# design.net
KiCad netlist of a schematic drawn in Altium Designer
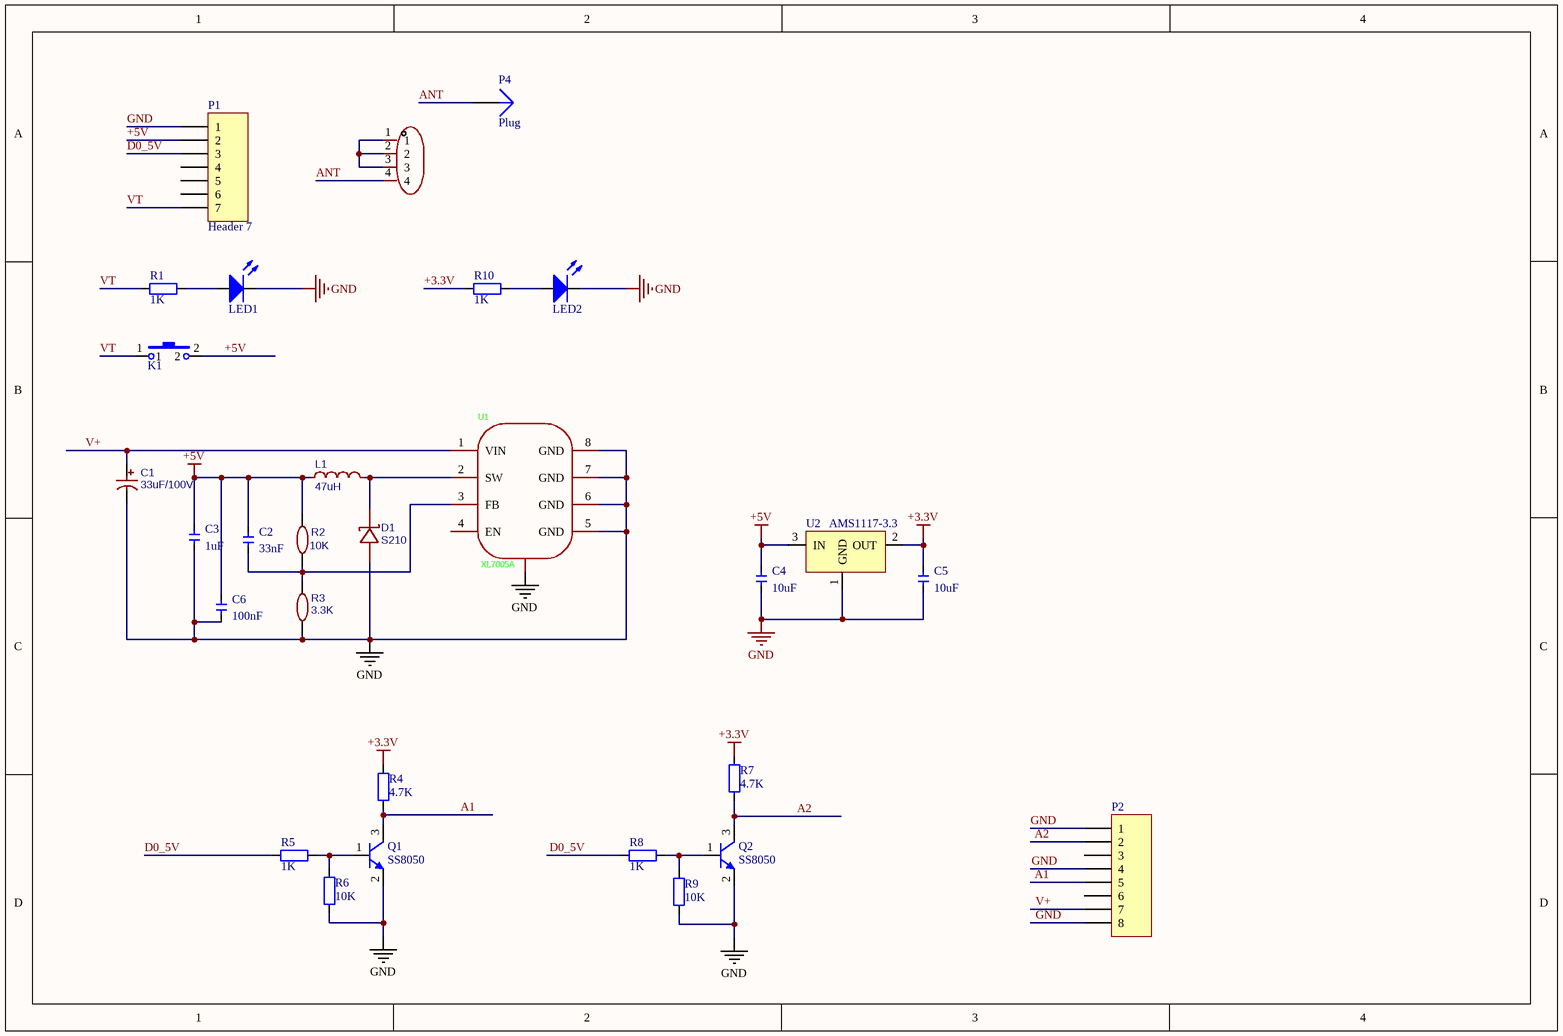
[diagram p0: 遥控.SchDoc]

(export (version "E")
  (design (tool "Eeschema 10.0.6"))
  (components
    (comp (ref "C1")
      (value "33uF/100V")
      (footprint "25V330UF-ZC")
      (fields
        (field (name "MANUFACTURER") "ValuePro")
        (field (name "MANUFACTURER PART") "470uF 35V 10*15Green high frequency")
      )
      (libsource (lib "altium-import") (part "root_3_470uF_"))
    )
    (comp (ref "C2")
      (value "33nF")
      (footprint "CAP-0603")
      (description "无极性电容")
      (fields (field (name "PUBLISHER") "Altium Limited"))
      (libsource (lib "Arrowy_Racing") (part "Cap"))
    )
    (comp (ref "C3")
      (value "1uF")
      (footprint "CAP-0603")
      (description "无极性电容")
      (fields (field (name "PUBLISHER") "Altium Limited"))
      (libsource (lib "Arrowy_Racing") (part "Cap"))
    )
    (comp (ref "C4")
      (value "10uF")
      (footprint "CAP-0603")
      (description "无极性电容")
      (fields (field (name "PUBLISHER") "Altium Limited"))
      (libsource (lib "Arrowy_Racing") (part "Cap"))
    )
    (comp (ref "C5")
      (value "10uF")
      (footprint "CAP-0603")
      (description "无极性电容")
      (fields (field (name "PUBLISHER") "Altium Limited"))
      (libsource (lib "Arrowy_Racing") (part "Cap"))
    )
    (comp (ref "C6")
      (value "100nF")
      (footprint "CAP-0603")
      (description "无极性电容")
      (fields (field (name "PUBLISHER") "Altium Limited"))
      (libsource (lib "Arrowy_Racing") (part "Cap"))
    )
    (comp (ref "D1")
      (value "S210")
      (footprint "SOD-123")
      (fields (field (name "MANUFACTURER PART") "B340A") (field (name "MANUFACTURER") "MDD"))
      (libsource (lib "altium-import") (part "root_3_B340A_"))
    )
    (comp (ref "K1")
      (value "SW-PB")
      (footprint "SW-SMD_4P-L6.0-W6.0")
      (description "微动开关")
      (fields (field (name "SUPPLITER PART") "C961737") (field (name "PUBLISHER") "Altium Limited"))
      (libsource (lib "Arrowy_Racing") (part "SW-PB"))
    )
    (comp (ref "L1")
      (value "47uH")
      (footprint "IND-SMD_L4.0-W4.0_FNR4012S")
      (fields (field (name "MANUFACTURER") "SXN") (field (name "MANUFACTURER PART") "SMDRI127-680MT"))
      (libsource (lib "altium-import") (part "root_0_68uH_"))
    )
    (comp (ref "LED1")
      (value "LED")
      (footprint "LED_0805")
      (description "发光二极管")
      (fields (field (name "PUBLISHER") "Altium Limited"))
      (libsource (lib "Arrowy_Racing") (part "LED"))
    )
    (comp (ref "LED2")
      (value "LED")
      (footprint "LED_0805")
      (description "发光二极管")
      (fields (field (name "PUBLISHER") "Altium Limited"))
      (libsource (lib "Arrowy_Racing") (part "LED"))
    )
    (comp (ref "P1")
      (value "Header 7")
      (footprint "HDR1X7")
      (description "Header, 7-Pin")
      (fields (field (name "PUBLISHER") "Altium Limited"))
      (libsource (lib "Miscellaneous Connectors") (part "Header 7"))
    )
    (comp (ref "P2")
      (value "Header 8")
      (footprint "XH2.54-W-8P")
      (description "Header, 8-Pin")
      (fields (field (name "PUBLISHER") "Altium Limited"))
      (libsource (lib "Miscellaneous Connectors") (part "Header 8"))
    )
    (comp (ref "P4")
      (value "Plug")
      (footprint "HEADER_1")
      (description "安装孔")
      (fields (field (name "PUBLISHER") "Altium Limited"))
      (libsource (lib "Arrowy_Racing") (part "Plug"))
    )
    (comp (ref "Q1")
      (value "SS8050")
      (footprint "SOT-23")
      (description "NPN贴片三极管")
      (fields (field (name "PUBLISHER") "Altium Limited"))
      (libsource (lib "Arrowy_Racing") (part "SS8050"))
    )
    (comp (ref "Q2")
      (value "SS8050")
      (footprint "SOT-23")
      (description "NPN贴片三极管")
      (fields (field (name "PUBLISHER") "Altium Limited"))
      (libsource (lib "Arrowy_Racing") (part "SS8050"))
    )
    (comp (ref "R1")
      (value "1K")
      (footprint "0603 - duplicate1")
      (description "贴片电阻")
      (fields (field (name "PUBLISHER") "Altium Limited"))
      (libsource (lib "") (part "Res_1"))
    )
    (comp (ref "R2")
      (value "10K")
      (footprint "0603 - duplicate1")
      (fields (field (name "MANUFACTURER") "UniOhm") (field (name "MANUFACTURER PART") "0603WAF1001T5E"))
      (libsource (lib "altium-import") (part "root_1_1K_"))
    )
    (comp (ref "R3")
      (value "3.3K")
      (footprint "0603 - duplicate1")
      (fields (field (name "MANUFACTURER") "UniOhm") (field (name "MANUFACTURER PART") "0603WAF3001T5E"))
      (libsource (lib "altium-import") (part "root_3_3K_"))
    )
    (comp (ref "R4")
      (value "4.7K")
      (footprint "0603 - duplicate1")
      (description "贴片电阻")
      (fields (field (name "PUBLISHER") "Altium Limited"))
      (libsource (lib "") (part "Res_3"))
    )
    (comp (ref "R5")
      (value "1K")
      (footprint "0603 - duplicate1")
      (description "贴片电阻")
      (fields (field (name "PUBLISHER") "Altium Limited"))
      (libsource (lib "") (part "Res_2"))
    )
    (comp (ref "R6")
      (value "10K")
      (footprint "0603 - duplicate1")
      (description "贴片电阻")
      (fields (field (name "PUBLISHER") "Altium Limited"))
      (libsource (lib "Arrowy_Racing") (part "Res"))
    )
    (comp (ref "R7")
      (value "4.7K")
      (footprint "0603 - duplicate1")
      (description "贴片电阻")
      (fields (field (name "PUBLISHER") "Altium Limited"))
      (libsource (lib "") (part "Res_3"))
    )
    (comp (ref "R8")
      (value "1K")
      (footprint "0603 - duplicate1")
      (description "贴片电阻")
      (fields (field (name "PUBLISHER") "Altium Limited"))
      (libsource (lib "") (part "Res_2"))
    )
    (comp (ref "R9")
      (value "10K")
      (footprint "0603 - duplicate1")
      (description "贴片电阻")
      (fields (field (name "PUBLISHER") "Altium Limited"))
      (libsource (lib "Arrowy_Racing") (part "Res"))
    )
    (comp (ref "R10")
      (value "1K")
      (footprint "0603 - duplicate1")
      (description "贴片电阻")
      (fields (field (name "PUBLISHER") "Altium Limited"))
      (libsource (lib "") (part "Res_1"))
    )
    (comp (ref "RF1")
      (value "6GHz")
      (footprint "CONN-SMD_GT-RF1125A-01G")
      (fields
        (field (name "MANUFACTURER") "G-Switch(品赞)")
        (field (name "MANUFACTURER PART") "GT-RF1125A-01G")
      )
      (libsource (lib "altium-import") (part "root_0_GT-RF1125A-01G_"))
    )
    (comp (ref "U1")
      (value "XL7005A")
      (footprint "SOIC-8_L4.9-W3.9-P1.27-LS6.0-BL-EP3.1-1")
      (fields (field (name "MANUFACTURER") "XLSEMI(芯龙)"))
      (libsource (lib "altium-import") (part "root_0_XL7005A_"))
    )
    (comp (ref "U2")
      (value "AMS1117-3.3")
      (footprint "SOT89")
      (description "3.3V稳压芯片")
      (libsource (lib "Arrowy_Racing") (part "AMS1117"))
    )
  )
  (nets
    (net (code "1") (name "+3.3V") (class "Default")
      (node (ref "C5") (pin "2") (pinfunction "2_2") (pintype "passive"))
      (node (ref "R10") (pin "2") (pinfunction "2_2") (pintype "passive"))
      (node (ref "R4") (pin "1") (pinfunction "1_1") (pintype "passive"))
      (node (ref "R7") (pin "1") (pinfunction "1_1") (pintype "passive"))
      (node (ref "U2") (pin "2") (pinfunction "OUT_2") (pintype "passive"))
    )
    (net (code "2") (name "+5V") (class "Default")
      (node (ref "C2") (pin "2") (pinfunction "2_2") (pintype "passive"))
      (node (ref "C3") (pin "2") (pinfunction "2_2") (pintype "passive"))
      (node (ref "C4") (pin "2") (pinfunction "2_2") (pintype "passive"))
      (node (ref "C6") (pin "2") (pinfunction "2_2") (pintype "passive"))
      (node (ref "K1") (pin "2") (pinfunction "2_2") (pintype "passive"))
      (node (ref "L1") (pin "1") (pinfunction "1_1") (pintype "passive"))
      (node (ref "P1") (pin "2") (pinfunction "2_2") (pintype "passive"))
      (node (ref "R2") (pin "2") (pinfunction "2_2") (pintype "passive"))
      (node (ref "U2") (pin "3") (pinfunction "IN_3") (pintype "passive"))
    )
    (net (code "3") (name "/A1") (class "Default")
      (node (ref "P2") (pin "5") (pinfunction "5_5") (pintype "passive"))
      (node (ref "Q1") (pin "3") (pinfunction "C_3") (pintype "passive"))
      (node (ref "R4") (pin "2") (pinfunction "2_2") (pintype "passive"))
    )
    (net (code "4") (name "/A2") (class "Default")
      (node (ref "P2") (pin "2") (pinfunction "2_2") (pintype "passive"))
      (node (ref "Q2") (pin "3") (pinfunction "C_3") (pintype "passive"))
      (node (ref "R7") (pin "2") (pinfunction "2_2") (pintype "passive"))
    )
    (net (code "5") (name "/ANT") (class "Default")
      (node (ref "P4") (pin "1") (pinfunction "1_1") (pintype "passive"))
      (node (ref "RF1") (pin "4") (pinfunction "4_4") (pintype "passive"))
    )
    (net (code "6") (name "/D0_5V") (class "Default")
      (node (ref "P1") (pin "3") (pinfunction "3_3") (pintype "passive"))
      (node (ref "R5") (pin "1") (pinfunction "1_1") (pintype "passive"))
      (node (ref "R8") (pin "1") (pinfunction "1_1") (pintype "passive"))
    )
    (net (code "7") (name "/V+") (class "Default")
      (node (ref "C1") (pin "1") (pinfunction "1_1") (pintype "passive"))
      (node (ref "P2") (pin "7") (pinfunction "7_7") (pintype "passive"))
      (node (ref "U1") (pin "1") (pinfunction "VIN_1") (pintype "passive"))
    )
    (net (code "8") (name "/VT") (class "Default")
      (node (ref "K1") (pin "1") (pinfunction "1_1") (pintype "passive"))
      (node (ref "P1") (pin "7") (pinfunction "7_7") (pintype "passive"))
      (node (ref "R1") (pin "2") (pinfunction "2_2") (pintype "passive"))
    )
    (net (code "9") (name "GND") (class "Default")
      (node (ref "C1") (pin "2") (pinfunction "2_2") (pintype "passive"))
      (node (ref "C3") (pin "1") (pinfunction "1_1") (pintype "passive"))
      (node (ref "C4") (pin "1") (pinfunction "1_1") (pintype "passive"))
      (node (ref "C5") (pin "1") (pinfunction "1_1") (pintype "passive"))
      (node (ref "C6") (pin "1") (pinfunction "1_1") (pintype "passive"))
      (node (ref "D1") (pin "2") (pinfunction "A_2") (pintype "passive"))
      (node (ref "LED1") (pin "2") (pinfunction "K_2") (pintype "passive"))
      (node (ref "LED2") (pin "2") (pinfunction "K_2") (pintype "passive"))
      (node (ref "P1") (pin "1") (pinfunction "1_1") (pintype "passive"))
      (node (ref "P2") (pin "1") (pinfunction "1_1") (pintype "passive"))
      (node (ref "P2") (pin "4") (pinfunction "4_4") (pintype "passive"))
      (node (ref "P2") (pin "8") (pinfunction "8_8") (pintype "passive"))
      (node (ref "Q1") (pin "2") (pinfunction "E_2") (pintype "passive"))
      (node (ref "Q2") (pin "2") (pinfunction "E_2") (pintype "passive"))
      (node (ref "R3") (pin "2") (pinfunction "2_2") (pintype "passive"))
      (node (ref "R6") (pin "1") (pinfunction "1_1") (pintype "passive"))
      (node (ref "R9") (pin "1") (pinfunction "1_1") (pintype "passive"))
      (node (ref "U1") (pin "5") (pinfunction "GND_5") (pintype "passive"))
      (node (ref "U1") (pin "6") (pinfunction "GND_6") (pintype "passive"))
      (node (ref "U1") (pin "7") (pinfunction "GND_7") (pintype "passive"))
      (node (ref "U1") (pin "8") (pinfunction "GND_8") (pintype "passive"))
      (node (ref "U1") (pin "9") (pinfunction "9_9") (pintype "passive"))
      (node (ref "U2") (pin "1") (pinfunction "GND_1") (pintype "passive"))
    )
    (net (code "10") (name "Net-(D1-K)") (class "Default")
      (node (ref "D1") (pin "1") (pinfunction "K_1") (pintype "passive"))
      (node (ref "L1") (pin "2") (pinfunction "2_2") (pintype "passive"))
      (node (ref "U1") (pin "2") (pinfunction "SW_2") (pintype "passive"))
    )
    (net (code "11") (name "Net-(LED1-A)") (class "Default")
      (node (ref "LED1") (pin "1") (pinfunction "A_1") (pintype "passive"))
      (node (ref "R1") (pin "1") (pinfunction "1_1") (pintype "passive"))
    )
    (net (code "12") (name "Net-(LED2-A)") (class "Default")
      (node (ref "LED2") (pin "1") (pinfunction "A_1") (pintype "passive"))
      (node (ref "R10") (pin "1") (pinfunction "1_1") (pintype "passive"))
    )
    (net (code "13") (name "Net-(Q1-B)") (class "Default")
      (node (ref "Q1") (pin "1") (pinfunction "B_1") (pintype "passive"))
      (node (ref "R5") (pin "2") (pinfunction "2_2") (pintype "passive"))
      (node (ref "R6") (pin "2") (pinfunction "2_2") (pintype "passive"))
    )
    (net (code "14") (name "Net-(Q2-B)") (class "Default")
      (node (ref "Q2") (pin "1") (pinfunction "B_1") (pintype "passive"))
      (node (ref "R8") (pin "2") (pinfunction "2_2") (pintype "passive"))
      (node (ref "R9") (pin "2") (pinfunction "2_2") (pintype "passive"))
    )
    (net (code "15") (name "Net-(RF1-Pad1)") (class "Default")
      (node (ref "RF1") (pin "1") (pinfunction "1_1") (pintype "passive"))
      (node (ref "RF1") (pin "2") (pinfunction "2_2") (pintype "passive"))
      (node (ref "RF1") (pin "3") (pinfunction "3_3") (pintype "passive"))
    )
    (net (code "16") (name "Net-(U1-FB)") (class "Default")
      (node (ref "C2") (pin "1") (pinfunction "1_1") (pintype "passive"))
      (node (ref "R2") (pin "1") (pinfunction "1_1") (pintype "passive"))
      (node (ref "R3") (pin "1") (pinfunction "1_1") (pintype "passive"))
      (node (ref "U1") (pin "3") (pinfunction "FB_3") (pintype "passive"))
    )
    (net (code "17") (name "unconnected-(P1-Pad4)") (class "Default")
      (node (ref "P1") (pin "4") (pinfunction "4_4") (pintype "passive"))
    )
    (net (code "18") (name "unconnected-(P1-Pad5)") (class "Default")
      (node (ref "P1") (pin "5") (pinfunction "5_5") (pintype "passive"))
    )
    (net (code "19") (name "unconnected-(P1-Pad6)") (class "Default")
      (node (ref "P1") (pin "6") (pinfunction "6_6") (pintype "passive"))
    )
    (net (code "20") (name "unconnected-(P2-Pad3)") (class "Default")
      (node (ref "P2") (pin "3") (pinfunction "3_3") (pintype "passive"))
    )
    (net (code "21") (name "unconnected-(P2-Pad6)") (class "Default")
      (node (ref "P2") (pin "6") (pinfunction "6_6") (pintype "passive"))
    )
    (net (code "22") (name "unconnected-(U1-EN-Pad4)") (class "Default")
      (node (ref "U1") (pin "4") (pinfunction "EN_4") (pintype "passive"))
    )
  )
)
